# 0-30V_Stabilized_PSU_Mk_10.net
KiCad netlist of a schematic drawn in EAGLE
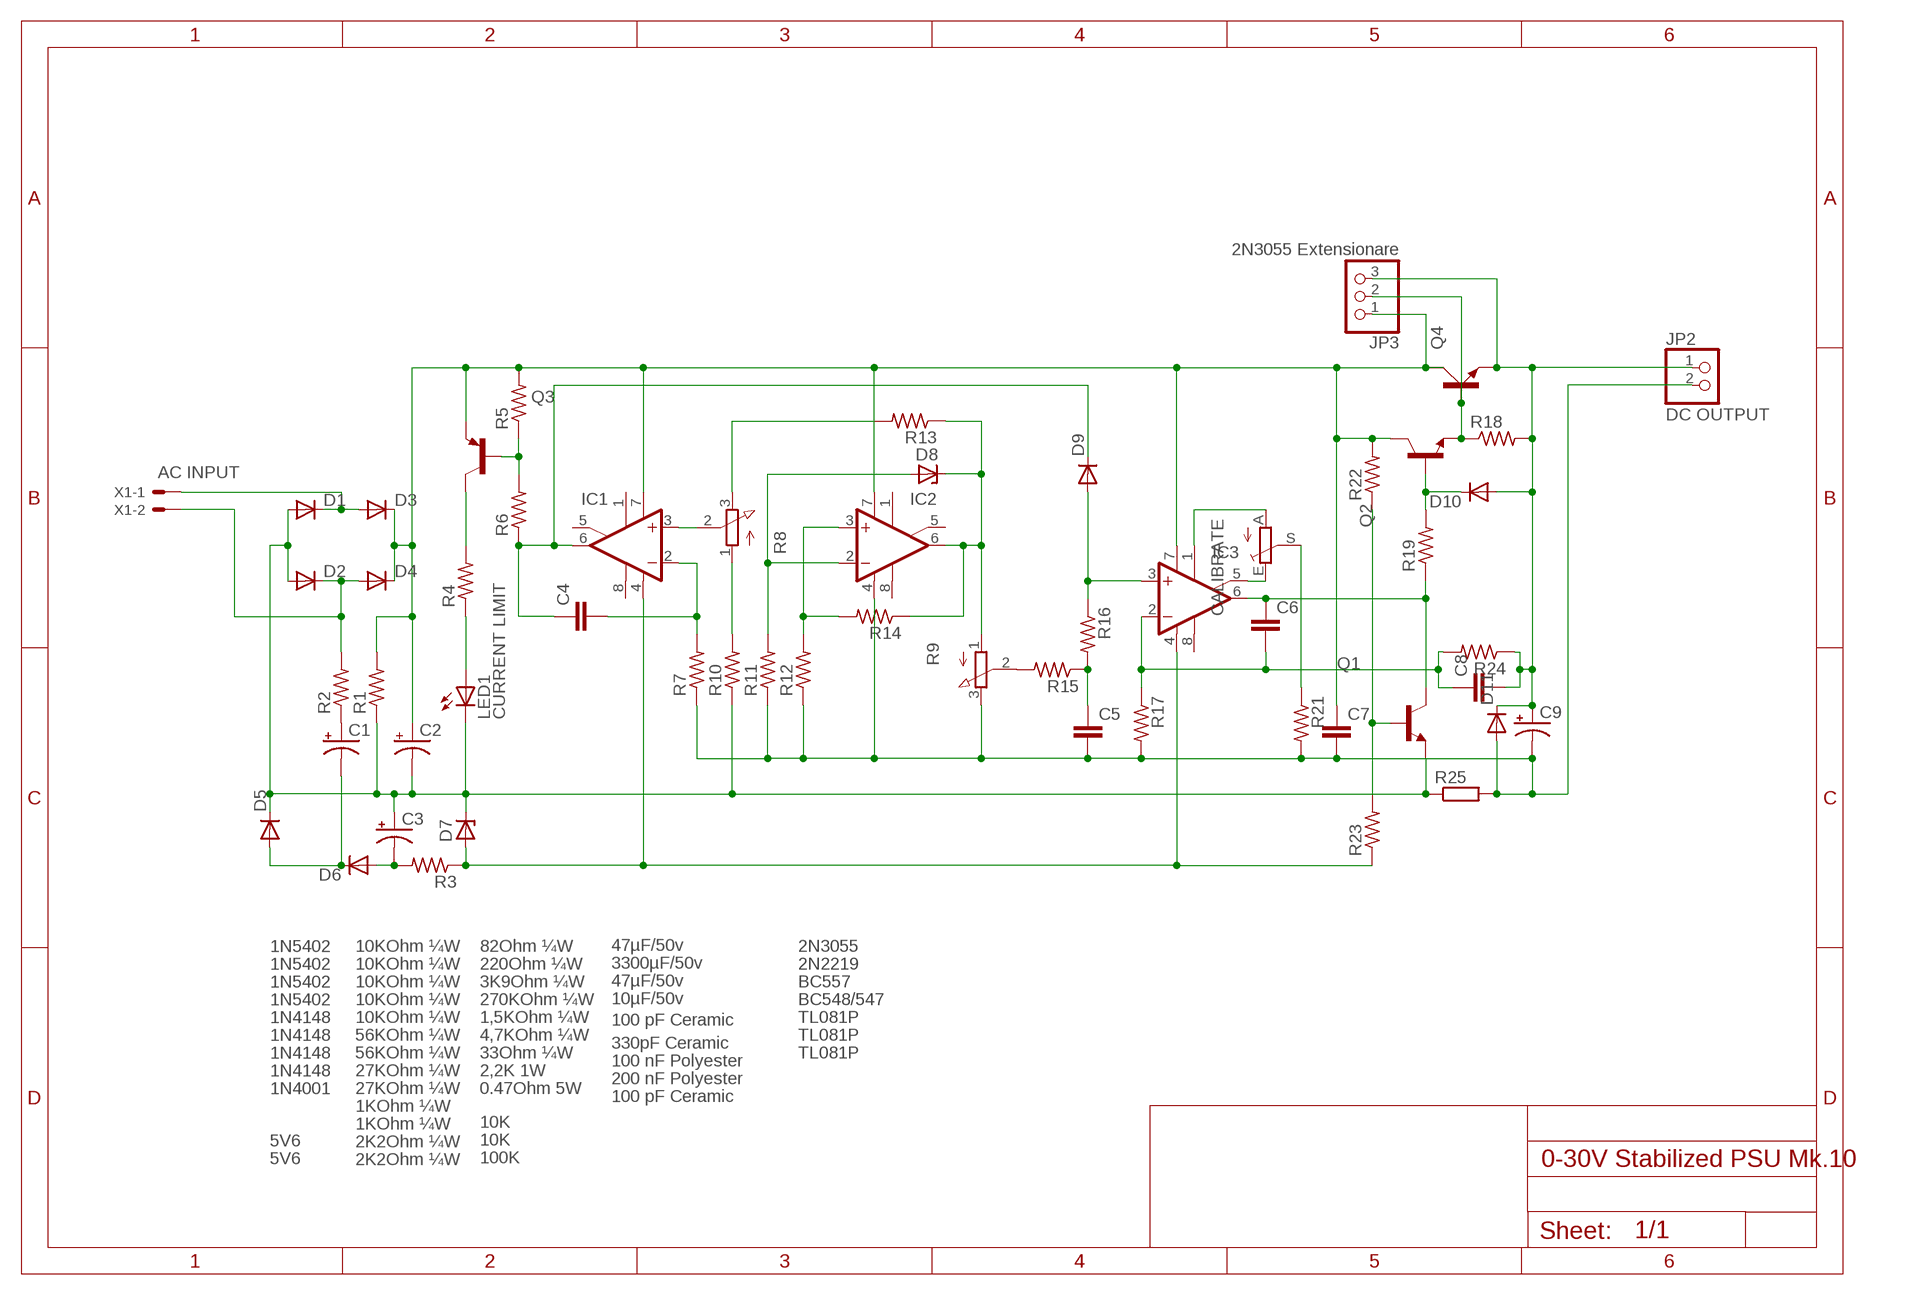
[diagram p0: schematic, sheet 1]

(export (version "E")
  (design (tool "Eeschema 10.0.6"))
  (components
    (comp (ref "C1")
      (value "47µF/50v")
      (footprint "eagle-import:TT2D4")
      (libsource (lib "eagle-import") (part "CPOL-USTT2D4"))
    )
    (comp (ref "C2")
      (value "3300µF/50v")
      (footprint "eagle-import:EB20D")
      (libsource (lib "eagle-import") (part "CPOL-USE10-20"))
    )
    (comp (ref "C3")
      (value "47µF/50v")
      (footprint "eagle-import:TT2D4")
      (libsource (lib "eagle-import") (part "CPOL-USTT2D4"))
    )
    (comp (ref "C4")
      (value "330pF Ceramic")
      (footprint "eagle-import:C025-024X044")
      (libsource (lib "eagle-import") (part "C-EU025-024X044"))
    )
    (comp (ref "C5")
      (value "100 nF Polyester")
      (footprint "eagle-import:C050-025X075")
      (libsource (lib "eagle-import") (part "C-EU050-025X075"))
    )
    (comp (ref "C6")
      (value "100 pF Ceramic")
      (footprint "eagle-import:C050-024X044")
      (libsource (lib "eagle-import") (part "C-EU050-024X044"))
    )
    (comp (ref "C7")
      (value "200 nF Polyester")
      (footprint "eagle-import:C075-032X103")
      (libsource (lib "eagle-import") (part "C-EU075-032X103"))
    )
    (comp (ref "C8")
      (value "100 pF Ceramic")
      (footprint "eagle-import:C050-024X044")
      (libsource (lib "eagle-import") (part "C-EU050-024X044"))
    )
    (comp (ref "C9")
      (value "10µF/50v")
      (footprint "eagle-import:E5-4")
      (libsource (lib "eagle-import") (part "resistor_CPOL-USE5-4"))
    )
    (comp (ref "CALIBRATE")
      (value "100K")
      (footprint "eagle-import:CA6V")
      (libsource (lib "eagle-import") (part "TRIM_EU-CA6V"))
    )
    (comp (ref "D1")
      (value "1N5402")
      (footprint "eagle-import:DO201-15")
      (libsource (lib "eagle-import") (part "1N5400"))
    )
    (comp (ref "D2")
      (value "1N5402")
      (footprint "eagle-import:DO201-15")
      (libsource (lib "eagle-import") (part "1N5400"))
    )
    (comp (ref "D3")
      (value "1N5402")
      (footprint "eagle-import:DO201-15")
      (libsource (lib "eagle-import") (part "1N5400"))
    )
    (comp (ref "D4")
      (value "1N5402")
      (footprint "eagle-import:DO201-15")
      (libsource (lib "eagle-import") (part "1N5400"))
    )
    (comp (ref "D5")
      (value "1N4148")
      (footprint "eagle-import:DO35-10")
      (libsource (lib "eagle-import") (part "1N4148DO35-10"))
    )
    (comp (ref "D6")
      (value "1N4148")
      (footprint "eagle-import:DO35-10")
      (libsource (lib "eagle-import") (part "1N4148DO35-10"))
    )
    (comp (ref "D7")
      (value "5V6")
      (footprint "eagle-import:DO34Z7")
      (libsource (lib "eagle-import") (part "ZENER-DIODEDO34-7"))
    )
    (comp (ref "D8")
      (value "5V6")
      (footprint "eagle-import:DO34Z7")
      (libsource (lib "eagle-import") (part "ZENER-DIODEDO34-7"))
    )
    (comp (ref "D9")
      (value "1N4148")
      (footprint "eagle-import:DO35-7")
      (libsource (lib "eagle-import") (part "1N4148DO35-7"))
    )
    (comp (ref "D10")
      (value "1N4148")
      (footprint "eagle-import:DO35-7")
      (libsource (lib "eagle-import") (part "1N4148DO35-7"))
    )
    (comp (ref "D11")
      (value "1N4001")
      (footprint "eagle-import:DO35-7")
      (libsource (lib "eagle-import") (part "1N4148DO35-7"))
    )
    (comp (ref "IC1")
      (value "TL081P")
      (footprint "eagle-import:DIL08")
      (libsource (lib "eagle-import") (part "TL081P"))
    )
    (comp (ref "IC2")
      (value "TL081P")
      (footprint "eagle-import:DIL08")
      (libsource (lib "eagle-import") (part "TL081P"))
    )
    (comp (ref "IC3")
      (value "TL081P")
      (footprint "eagle-import:DIL08")
      (libsource (lib "eagle-import") (part "TL081P"))
    )
    (comp (ref "JP2")
      (value "DC OUTPUT")
      (footprint "eagle-import:1X02")
      (libsource (lib "eagle-import") (part "PINHD-1X2"))
    )
    (comp (ref "JP3")
      (value "2N3055 Extensionare")
      (footprint "eagle-import:1X03")
      (libsource (lib "eagle-import") (part "PINHD-1X3"))
    )
    (comp (ref "LED1")
      (value "CURRENT LIMIT")
      (footprint "eagle-import:LED3MM")
      (libsource (lib "eagle-import") (part "LED3MM"))
    )
    (comp (ref "Q1")
      (value "BC548/547")
      (footprint "eagle-import:TO92-EBC")
      (libsource (lib "eagle-import") (part "BC548"))
    )
    (comp (ref "Q2")
      (value "2N2219")
      (footprint "eagle-import:TO5")
      (libsource (lib "eagle-import") (part "2N2219"))
    )
    (comp (ref "Q3")
      (value "BC557")
      (footprint "eagle-import:TO92-EBC")
      (libsource (lib "eagle-import") (part "BC557"))
    )
    (comp (ref "Q4")
      (value "2N3055")
      (footprint "eagle-import:TO3A")
      (libsource (lib "eagle-import") (part "2N3055"))
    )
    (comp (ref "R1")
      (value "2,2K 1W")
      (footprint "eagle-import:P0613_15")
      (libsource (lib "eagle-import") (part "resistor_R-US_0613/15"))
    )
    (comp (ref "R2")
      (value "82Ohm ¼W")
      (footprint "eagle-import:0204_7")
      (libsource (lib "eagle-import") (part "R-US_0204/7"))
    )
    (comp (ref "R3")
      (value "220Ohm ¼W")
      (footprint "eagle-import:0204_7")
      (libsource (lib "eagle-import") (part "R-US_0204/7"))
    )
    (comp (ref "R4")
      (value "3K9Ohm ¼W")
      (footprint "eagle-import:0204_7")
      (libsource (lib "eagle-import") (part "R-US_0204/7"))
    )
    (comp (ref "R5")
      (value "2K2Ohm ¼W")
      (footprint "eagle-import:0204_7")
      (libsource (lib "eagle-import") (part "R-US_0204/7"))
    )
    (comp (ref "R6")
      (value "10KOhm ¼W")
      (footprint "eagle-import:0204_7")
      (libsource (lib "eagle-import") (part "R-US_0204/7"))
    )
    (comp (ref "R7")
      (value "10KOhm ¼W")
      (footprint "eagle-import:0204_7")
      (libsource (lib "eagle-import") (part "R-US_0204/7"))
    )
    (comp (ref "R8")
      (value "10K")
      (footprint "eagle-import:3RP_1610N")
      (libsource (lib "eagle-import") (part "3RP/1610N"))
    )
    (comp (ref "R9")
      (value "10K")
      (footprint "eagle-import:3RP_1610N")
      (libsource (lib "eagle-import") (part "3RP/1610N"))
    )
    (comp (ref "R10")
      (value "33Ohm ¼W")
      (footprint "eagle-import:0204_7")
      (libsource (lib "eagle-import") (part "R-US_0204/7"))
    )
    (comp (ref "R11")
      (value "4,7KOhm ¼W")
      (footprint "eagle-import:0204_7")
      (libsource (lib "eagle-import") (part "R-US_0204/7"))
    )
    (comp (ref "R12")
      (value "10KOhm ¼W")
      (footprint "eagle-import:0204_7")
      (libsource (lib "eagle-import") (part "R-US_0204/7"))
    )
    (comp (ref "R13")
      (value "56KOhm ¼W")
      (footprint "eagle-import:0204_7")
      (libsource (lib "eagle-import") (part "R-US_0204/7"))
    )
    (comp (ref "R14")
      (value "10KOhm ¼W")
      (footprint "eagle-import:0204_7")
      (libsource (lib "eagle-import") (part "R-US_0204/7"))
    )
    (comp (ref "R15")
      (value "27KOhm ¼W")
      (footprint "eagle-import:0204_7")
      (libsource (lib "eagle-import") (part "R-US_0204/7"))
    )
    (comp (ref "R16")
      (value "2K2Ohm ¼W")
      (footprint "eagle-import:0204_7")
      (libsource (lib "eagle-import") (part "R-US_0204/7"))
    )
    (comp (ref "R17")
      (value "27KOhm ¼W")
      (footprint "eagle-import:0204_7")
      (libsource (lib "eagle-import") (part "R-US_0204/7"))
    )
    (comp (ref "R18")
      (value "1KOhm ¼W")
      (footprint "eagle-import:0207_2V")
      (libsource (lib "eagle-import") (part "R-US_0207/2V"))
    )
    (comp (ref "R19")
      (value "1KOhm ¼W")
      (footprint "eagle-import:0207_2V")
      (libsource (lib "eagle-import") (part "R-US_0207/2V"))
    )
    (comp (ref "R21")
      (value "270KOhm ¼W")
      (footprint "eagle-import:0204_7")
      (libsource (lib "eagle-import") (part "R-US_0204/7"))
    )
    (comp (ref "R22")
      (value "10KOhm ¼W")
      (footprint "eagle-import:0204_7")
      (libsource (lib "eagle-import") (part "R-US_0204/7"))
    )
    (comp (ref "R23")
      (value "1,5KOhm ¼W")
      (footprint "eagle-import:0204_7")
      (libsource (lib "eagle-import") (part "R-US_0204/7"))
    )
    (comp (ref "R24")
      (value "56KOhm ¼W")
      (footprint "eagle-import:0204_7")
      (libsource (lib "eagle-import") (part "R-US_0204/7"))
    )
    (comp (ref "R25")
      (value "0.47Ohm 5W")
      (footprint "eagle-import:VTA54")
      (libsource (lib "eagle-import") (part "R-EU_VTA54"))
    )
    (comp (ref "X1")
      (value "AC INPUT")
      (footprint "eagle-import:22-23-2021")
      (fields (field (name "MF") "MOLEX") (field (name "MPN") "22-23-2021"))
      (libsource (lib "eagle-import") (part "22-23-2021"))
    )
  )
  (nets
    (net (code "1") (name "Net-(C1-Pad+)") (class "Default")
      (node (ref "C1") (pin "+") (pinfunction "+_+") (pintype "passive"))
      (node (ref "R2") (pin "1") (pinfunction "1_1") (pintype "passive"))
    )
    (net (code "2") (name "Net-(C1-Pad-)") (class "Default")
      (node (ref "C1") (pin "-") (pinfunction "-_-") (pintype "passive"))
      (node (ref "D5") (pin "A") (pinfunction "A_A") (pintype "passive"))
      (node (ref "D6") (pin "C") (pinfunction "C_C") (pintype "passive"))
    )
    (net (code "3") (name "Net-(C3-Pad-)") (class "Default")
      (node (ref "C3") (pin "-") (pinfunction "-_-") (pintype "passive"))
      (node (ref "D6") (pin "A") (pinfunction "A_A") (pintype "passive"))
      (node (ref "R3") (pin "2") (pinfunction "2_2") (pintype "passive"))
    )
    (net (code "4") (name "Net-(C5-Pad1)") (class "Default")
      (node (ref "C5") (pin "1") (pinfunction "1_1") (pintype "passive"))
      (node (ref "R15") (pin "1") (pinfunction "1_1") (pintype "passive"))
      (node (ref "R16") (pin "2") (pinfunction "2_2") (pintype "passive"))
    )
    (net (code "5") (name "Net-(C8-Pad2)") (class "Default")
      (node (ref "C8") (pin "2") (pinfunction "2_2") (pintype "passive"))
      (node (ref "C9") (pin "+") (pinfunction "+_+") (pintype "passive"))
      (node (ref "D10") (pin "A") (pinfunction "A_A") (pintype "passive"))
      (node (ref "D11") (pin "C") (pinfunction "C_C") (pintype "passive"))
      (node (ref "JP2") (pin "1") (pinfunction "1_1") (pintype "passive"))
      (node (ref "JP3") (pin "3") (pinfunction "3_3") (pintype "passive"))
      (node (ref "Q4") (pin "E") (pinfunction "E_E") (pintype "passive"))
      (node (ref "R18") (pin "2") (pinfunction "2_2") (pintype "passive"))
      (node (ref "R24") (pin "1") (pinfunction "1_1") (pintype "passive"))
    )
    (net (code "6") (name "Net-(CALIBRATE-PadS)") (class "Default")
      (node (ref "CALIBRATE") (pin "S") (pinfunction "S_S") (pintype "passive"))
      (node (ref "R21") (pin "1") (pinfunction "1_1") (pintype "passive"))
    )
    (net (code "7") (name "Net-(IC1-+IN)") (class "Default")
      (node (ref "IC1") (pin "3") (pinfunction "+IN_3") (pintype "input"))
      (node (ref "R8") (pin "2") (pinfunction "S_2") (pintype "passive"))
    )
    (net (code "8") (name "Net-(IC1--IN)") (class "Default")
      (node (ref "C4") (pin "2") (pinfunction "2_2") (pintype "passive"))
      (node (ref "IC1") (pin "2") (pinfunction "-IN_2") (pintype "input"))
      (node (ref "R7") (pin "2") (pinfunction "2_2") (pintype "passive"))
    )
    (net (code "9") (name "Net-(IC1-OUT)") (class "Default")
      (node (ref "C4") (pin "1") (pinfunction "1_1") (pintype "passive"))
      (node (ref "D9") (pin "C") (pinfunction "C_C") (pintype "passive"))
      (node (ref "IC1") (pin "6") (pinfunction "OUT_6") (pintype "output"))
      (node (ref "R6") (pin "1") (pinfunction "1_1") (pintype "passive"))
    )
    (net (code "10") (name "Net-(IC1-V+)") (class "Default")
      (node (ref "C2") (pin "+") (pinfunction "+_+") (pintype "passive"))
      (node (ref "C7") (pin "1") (pinfunction "1_1") (pintype "passive"))
      (node (ref "D3") (pin "C") (pinfunction "C_C") (pintype "passive"))
      (node (ref "D4") (pin "C") (pinfunction "C_C") (pintype "passive"))
      (node (ref "IC1") (pin "7") (pinfunction "V+_7") (pintype "power_in"))
      (node (ref "IC2") (pin "7") (pinfunction "V+_7") (pintype "power_in"))
      (node (ref "IC3") (pin "7") (pinfunction "V+_7") (pintype "power_in"))
      (node (ref "JP3") (pin "1") (pinfunction "1_1") (pintype "passive"))
      (node (ref "Q2") (pin "3") (pinfunction "C_3") (pintype "passive"))
      (node (ref "Q3") (pin "E") (pinfunction "E_E") (pintype "passive"))
      (node (ref "Q4") (pin "C") (pinfunction "C_C") (pintype "passive"))
      (node (ref "Q4") (pin "C1") (pinfunction "C_C1") (pintype "passive"))
      (node (ref "R1") (pin "2") (pinfunction "2_2") (pintype "passive"))
      (node (ref "R22") (pin "2") (pinfunction "2_2") (pintype "passive"))
      (node (ref "R5") (pin "2") (pinfunction "2_2") (pintype "passive"))
    )
    (net (code "11") (name "Net-(IC1-V-)") (class "Default")
      (node (ref "D7") (pin "A") (pinfunction "A_A") (pintype "passive"))
      (node (ref "IC1") (pin "4") (pinfunction "V-_4") (pintype "power_in"))
      (node (ref "IC3") (pin "4") (pinfunction "V-_4") (pintype "power_in"))
      (node (ref "R23") (pin "1") (pinfunction "1_1") (pintype "passive"))
      (node (ref "R3") (pin "1") (pinfunction "1_1") (pintype "passive"))
    )
    (net (code "12") (name "Net-(IC2-+IN)") (class "Default")
      (node (ref "IC2") (pin "3") (pinfunction "+IN_3") (pintype "input"))
      (node (ref "R12") (pin "2") (pinfunction "2_2") (pintype "passive"))
      (node (ref "R14") (pin "2") (pinfunction "2_2") (pintype "passive"))
    )
    (net (code "13") (name "Net-(IC2--IN)") (class "Default")
      (node (ref "D8") (pin "A") (pinfunction "A_A") (pintype "passive"))
      (node (ref "IC2") (pin "2") (pinfunction "-IN_2") (pintype "input"))
      (node (ref "R11") (pin "2") (pinfunction "2_2") (pintype "passive"))
    )
    (net (code "14") (name "Net-(IC2-OUT)") (class "Default")
      (node (ref "D8") (pin "C") (pinfunction "C_C") (pintype "passive"))
      (node (ref "IC2") (pin "6") (pinfunction "OUT_6") (pintype "output"))
      (node (ref "R13") (pin "1") (pinfunction "1_1") (pintype "passive"))
      (node (ref "R14") (pin "1") (pinfunction "1_1") (pintype "passive"))
      (node (ref "R9") (pin "1") (pinfunction "A_1") (pintype "passive"))
    )
    (net (code "15") (name "Net-(IC2-V-)") (class "Default")
      (node (ref "C5") (pin "2") (pinfunction "2_2") (pintype "passive"))
      (node (ref "C7") (pin "2") (pinfunction "2_2") (pintype "passive"))
      (node (ref "C9") (pin "-") (pinfunction "-_-") (pintype "passive"))
      (node (ref "D11") (pin "A") (pinfunction "A_A") (pintype "passive"))
      (node (ref "IC2") (pin "4") (pinfunction "V-_4") (pintype "power_in"))
      (node (ref "JP2") (pin "2") (pinfunction "2_2") (pintype "passive"))
      (node (ref "R11") (pin "1") (pinfunction "1_1") (pintype "passive"))
      (node (ref "R12") (pin "1") (pinfunction "1_1") (pintype "passive"))
      (node (ref "R17") (pin "2") (pinfunction "2_2") (pintype "passive"))
      (node (ref "R21") (pin "2") (pinfunction "2_2") (pintype "passive"))
      (node (ref "R25") (pin "2") (pinfunction "2_2") (pintype "passive"))
      (node (ref "R7") (pin "1") (pinfunction "1_1") (pintype "passive"))
      (node (ref "R9") (pin "3") (pinfunction "E_3") (pintype "passive"))
    )
    (net (code "16") (name "Net-(IC3-+IN)") (class "Default")
      (node (ref "D9") (pin "A") (pinfunction "A_A") (pintype "passive"))
      (node (ref "IC3") (pin "3") (pinfunction "+IN_3") (pintype "input"))
      (node (ref "R16") (pin "1") (pinfunction "1_1") (pintype "passive"))
    )
    (net (code "17") (name "Net-(IC3--IN)") (class "Default")
      (node (ref "C6") (pin "2") (pinfunction "2_2") (pintype "passive"))
      (node (ref "C8") (pin "1") (pinfunction "1_1") (pintype "passive"))
      (node (ref "IC3") (pin "2") (pinfunction "-IN_2") (pintype "input"))
      (node (ref "R17") (pin "1") (pinfunction "1_1") (pintype "passive"))
      (node (ref "R24") (pin "2") (pinfunction "2_2") (pintype "passive"))
    )
    (net (code "18") (name "Net-(IC3-ON1)") (class "Default")
      (node (ref "CALIBRATE") (pin "A") (pinfunction "A_A") (pintype "passive"))
      (node (ref "IC3") (pin "1") (pinfunction "ON1_1") (pintype "passive"))
    )
    (net (code "19") (name "Net-(IC3-ON2)") (class "Default")
      (node (ref "CALIBRATE") (pin "E") (pinfunction "E_E") (pintype "passive"))
      (node (ref "IC3") (pin "5") (pinfunction "ON2_5") (pintype "passive"))
    )
    (net (code "20") (name "Net-(IC3-OUT)") (class "Default")
      (node (ref "C6") (pin "1") (pinfunction "1_1") (pintype "passive"))
      (node (ref "IC3") (pin "6") (pinfunction "OUT_6") (pintype "output"))
      (node (ref "Q1") (pin "C") (pinfunction "C_C") (pintype "passive"))
      (node (ref "R19") (pin "1") (pinfunction "1_1") (pintype "passive"))
    )
    (net (code "21") (name "Net-(LED1-C)") (class "Default")
      (node (ref "C2") (pin "-") (pinfunction "-_-") (pintype "passive"))
      (node (ref "C3") (pin "+") (pinfunction "+_+") (pintype "passive"))
      (node (ref "D1") (pin "A") (pinfunction "A_A") (pintype "passive"))
      (node (ref "D2") (pin "A") (pinfunction "A_A") (pintype "passive"))
      (node (ref "D5") (pin "C") (pinfunction "C_C") (pintype "passive"))
      (node (ref "D7") (pin "C") (pinfunction "C_C") (pintype "passive"))
      (node (ref "LED1") (pin "K") (pinfunction "C_K") (pintype "passive"))
      (node (ref "Q1") (pin "E") (pinfunction "E_E") (pintype "passive"))
      (node (ref "R1") (pin "1") (pinfunction "1_1") (pintype "passive"))
      (node (ref "R10") (pin "1") (pinfunction "1_1") (pintype "passive"))
      (node (ref "R25") (pin "1") (pinfunction "1_1") (pintype "passive"))
    )
    (net (code "22") (name "Net-(LED1-PadA)") (class "Default")
      (node (ref "LED1") (pin "A") (pinfunction "A_A") (pintype "passive"))
      (node (ref "R4") (pin "1") (pinfunction "1_1") (pintype "passive"))
    )
    (net (code "23") (name "Net-(Q1-PadB)") (class "Default")
      (node (ref "Q1") (pin "B") (pinfunction "B_B") (pintype "passive"))
      (node (ref "R22") (pin "1") (pinfunction "1_1") (pintype "passive"))
      (node (ref "R23") (pin "2") (pinfunction "2_2") (pintype "passive"))
    )
    (net (code "24") (name "Net-(Q2-B)") (class "Default")
      (node (ref "D10") (pin "C") (pinfunction "C_C") (pintype "passive"))
      (node (ref "Q2") (pin "2") (pinfunction "B_2") (pintype "passive"))
      (node (ref "R19") (pin "2") (pinfunction "2_2") (pintype "passive"))
    )
    (net (code "25") (name "Net-(Q2-E)") (class "Default")
      (node (ref "JP3") (pin "2") (pinfunction "2_2") (pintype "passive"))
      (node (ref "Q2") (pin "1") (pinfunction "E_1") (pintype "passive"))
      (node (ref "Q4") (pin "B") (pinfunction "B_B") (pintype "passive"))
      (node (ref "R18") (pin "1") (pinfunction "1_1") (pintype "passive"))
    )
    (net (code "26") (name "Net-(Q3-PadB)") (class "Default")
      (node (ref "Q3") (pin "B") (pinfunction "B_B") (pintype "passive"))
      (node (ref "R5") (pin "1") (pinfunction "1_1") (pintype "passive"))
      (node (ref "R6") (pin "2") (pinfunction "2_2") (pintype "passive"))
    )
    (net (code "27") (name "Net-(Q3-PadC)") (class "Default")
      (node (ref "Q3") (pin "C") (pinfunction "C_C") (pintype "passive"))
      (node (ref "R4") (pin "2") (pinfunction "2_2") (pintype "passive"))
    )
    (net (code "28") (name "Net-(R8-A)") (class "Default")
      (node (ref "R10") (pin "2") (pinfunction "2_2") (pintype "passive"))
      (node (ref "R8") (pin "1") (pinfunction "A_1") (pintype "passive"))
    )
    (net (code "29") (name "Net-(R8-E)") (class "Default")
      (node (ref "R13") (pin "2") (pinfunction "2_2") (pintype "passive"))
      (node (ref "R8") (pin "3") (pinfunction "E_3") (pintype "passive"))
    )
    (net (code "30") (name "Net-(R9-S)") (class "Default")
      (node (ref "R15") (pin "2") (pinfunction "2_2") (pintype "passive"))
      (node (ref "R9") (pin "2") (pinfunction "S_2") (pintype "passive"))
    )
    (net (code "31") (name "Net-(X1A-S)") (class "Default")
      (node (ref "D1") (pin "C") (pinfunction "C_C") (pintype "passive"))
      (node (ref "D3") (pin "A") (pinfunction "A_A") (pintype "passive"))
      (node (ref "X1") (pin "1") (pinfunction "S_1") (pintype "passive"))
    )
    (net (code "32") (name "Net-(X1B-S)") (class "Default")
      (node (ref "D2") (pin "C") (pinfunction "C_C") (pintype "passive"))
      (node (ref "D4") (pin "A") (pinfunction "A_A") (pintype "passive"))
      (node (ref "R2") (pin "2") (pinfunction "2_2") (pintype "passive"))
      (node (ref "X1") (pin "2") (pinfunction "S_2") (pintype "passive"))
    )
    (net (code "33") (name "unconnected-(IC1-ON1-Pad1)") (class "Default")
      (node (ref "IC1") (pin "1") (pinfunction "ON1_1") (pintype "passive"))
    )
    (net (code "34") (name "unconnected-(IC1-ON2-Pad5)") (class "Default")
      (node (ref "IC1") (pin "5") (pinfunction "ON2_5") (pintype "passive"))
    )
    (net (code "35") (name "unconnected-(IC1-OPT-Pad8)") (class "Default")
      (node (ref "IC1") (pin "8") (pinfunction "OPT_8") (pintype "passive"))
    )
    (net (code "36") (name "unconnected-(IC2-ON1-Pad1)") (class "Default")
      (node (ref "IC2") (pin "1") (pinfunction "ON1_1") (pintype "passive"))
    )
    (net (code "37") (name "unconnected-(IC2-ON2-Pad5)") (class "Default")
      (node (ref "IC2") (pin "5") (pinfunction "ON2_5") (pintype "passive"))
    )
    (net (code "38") (name "unconnected-(IC2-OPT-Pad8)") (class "Default")
      (node (ref "IC2") (pin "8") (pinfunction "OPT_8") (pintype "passive"))
    )
    (net (code "39") (name "unconnected-(IC3-OPT-Pad8)") (class "Default")
      (node (ref "IC3") (pin "8") (pinfunction "OPT_8") (pintype "passive"))
    )
  )
)
